# um982.net
KiCad netlist of a schematic drawn in Altium Designer
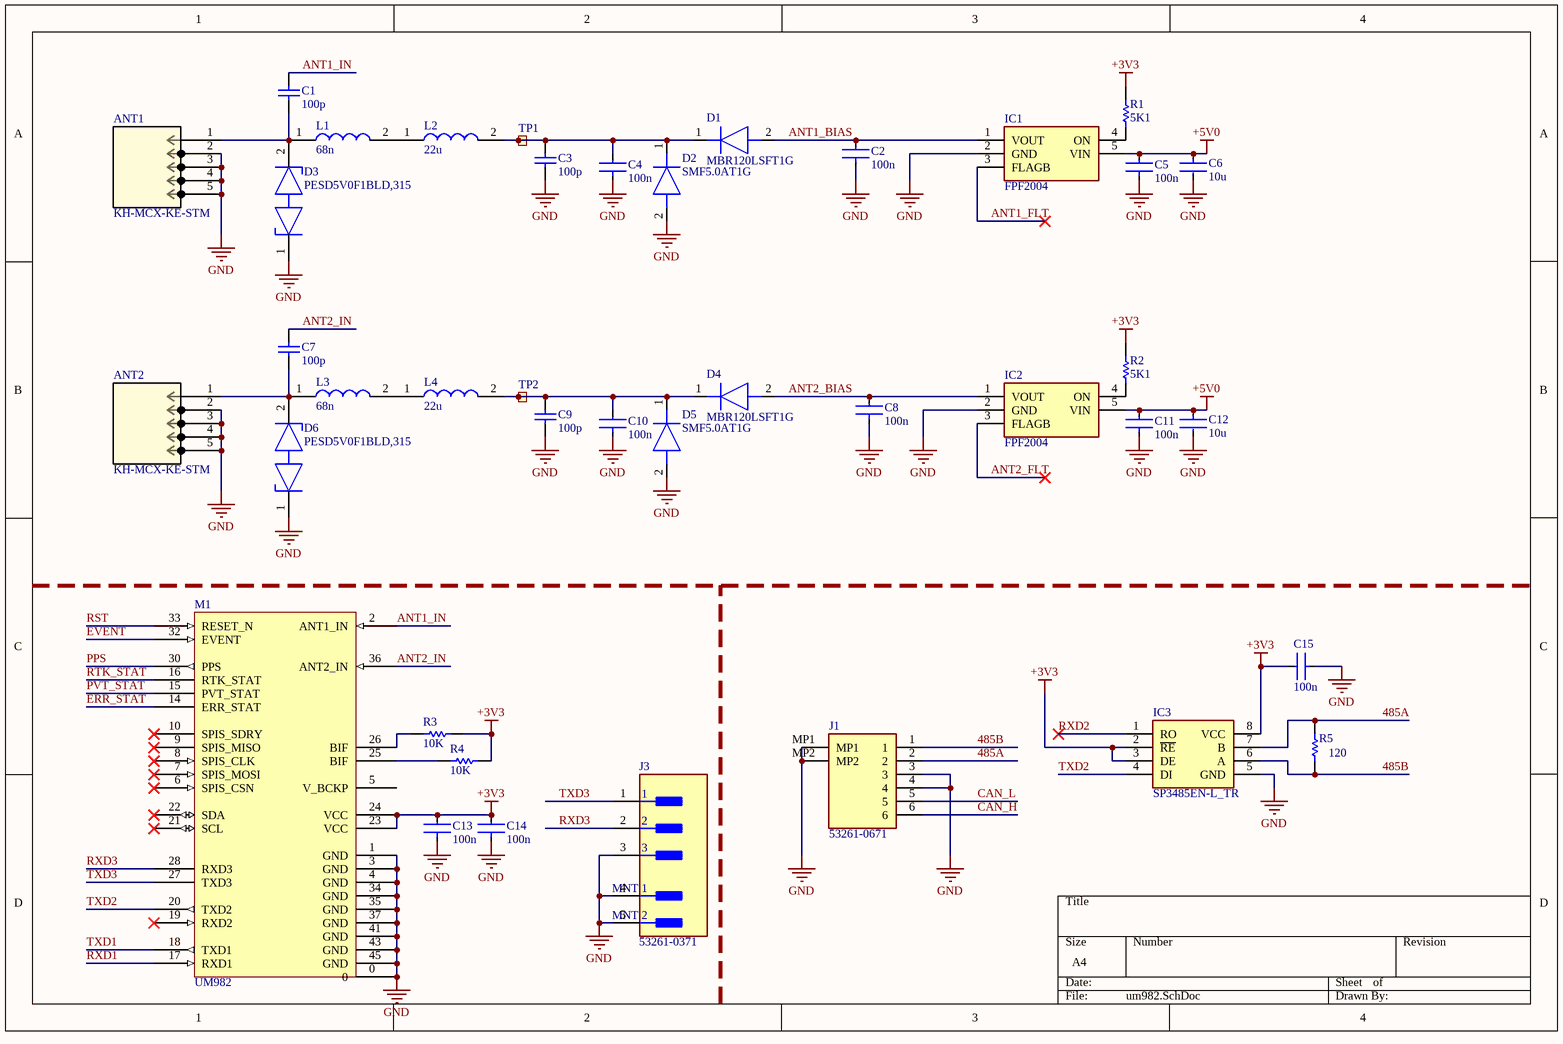
[diagram p0: um982.SchDoc]

(export (version "E")
  (design (tool "Eeschema 10.0.6"))
  (components
    (comp (ref "ANT1")
      (value "KH-MCX-KE-STM")
      (footprint "MCX-SMD_KH-MCX-KE-STM")
      (description "No Description Available")
      (fields
        (field (name "MANUFACTURER_PART_NUMBER") "919-415J-71P12G")
        (field (name "COPYRIGHT") "Copyright (C) 2025 Ultra Librarian. All rights reserved.")
      )
      (libsource (lib "UM982") (part "919-415J-71P12G"))
    )
    (comp (ref "ANT2")
      (value "KH-MCX-KE-STM")
      (footprint "MCX-SMD_KH-MCX-KE-STM")
      (description "No Description Available")
      (fields
        (field (name "MANUFACTURER_PART_NUMBER") "919-415J-71P12G")
        (field (name "COPYRIGHT") "Copyright (C) 2025 Ultra Librarian. All rights reserved.")
      )
      (libsource (lib "UM982") (part "919-415J-71P12G"))
    )
    (comp (ref "C1")
      (value "100p")
      (footprint "CAPC1005X55X25ML05T10")
      (fields (field (name "MANUFACTURER") "Murata") (field (name "PART NUMBER") "GRM1555C1H101JA01D"))
      (libsource (lib "Altium Content Vault") (part "CAP"))
    )
    (comp (ref "C2")
      (value "100n")
      (footprint "FP-C1005-050-0_05-IPC_C")
      (description "Multilayer Ceramic Capacitors 100nF ±10% 50V X7R SMD 0402")
      (fields (field (name "VOLTAGE") "50V") (field (name "TOLERANCE") "10%"))
      (libsource (lib "Altium Content Vault") (part "b4654b650e69147ec39a6b967a45e02"))
    )
    (comp (ref "C3")
      (value "100p")
      (footprint "CAPC1005X55X25ML05T10")
      (fields (field (name "MANUFACTURER") "Murata") (field (name "PART NUMBER") "GRM1555C1H101JA01D"))
      (libsource (lib "Altium Content Vault") (part "CAP"))
    )
    (comp (ref "C4")
      (value "100n")
      (footprint "FP-C1005-050-0_05-IPC_A")
      (description "Multilayer Ceramic Capacitors 100nF ±10% 50V X7R SMD 0402")
      (fields (field (name "VOLTAGE") "50V") (field (name "TOLERANCE") "10%"))
      (libsource (lib "Altium Content Vault") (part "b4654b650e69147ec39a6b967a45e02"))
    )
    (comp (ref "C5")
      (value "100n")
      (footprint "FP-C1005-050-0_05-IPC_C")
      (description "Multilayer Ceramic Capacitors 100nF ±10% 50V X7R SMD 0402")
      (fields (field (name "VOLTAGE") "50V") (field (name "TOLERANCE") "10%"))
      (libsource (lib "Altium Content Vault") (part "b4654b650e69147ec39a6b967a45e02"))
    )
    (comp (ref "C6")
      (value "10u")
      (footprint "FP-C1608-080-IPC_A")
      (description "CAP CER 10UF 25V X5R 0603")
      (fields (field (name "TOLERANCE") "20%") (field (name "Comment") "C1608X5R1E106M080AC"))
      (libsource (lib "Altium Content Vault") (part "11868f565c42a9108669ba33697ecf6"))
    )
    (comp (ref "C7")
      (value "100p")
      (footprint "CAPC1005X55X25ML05T10")
      (fields (field (name "MANUFACTURER") "Murata") (field (name "PART NUMBER") "GRM1555C1H101JA01D"))
      (libsource (lib "Altium Content Vault") (part "CAP"))
    )
    (comp (ref "C8")
      (value "100n")
      (footprint "FP-C1005-050-0_05-IPC_C")
      (description "Multilayer Ceramic Capacitors 100nF ±10% 50V X7R SMD 0402")
      (fields (field (name "VOLTAGE") "50V") (field (name "TOLERANCE") "10%"))
      (libsource (lib "Altium Content Vault") (part "b4654b650e69147ec39a6b967a45e02"))
    )
    (comp (ref "C9")
      (value "100p")
      (footprint "CAPC1005X55X25ML05T10")
      (fields (field (name "MANUFACTURER") "Murata") (field (name "PART NUMBER") "GRM1555C1H101JA01D"))
      (libsource (lib "Altium Content Vault") (part "CAP"))
    )
    (comp (ref "C10")
      (value "100n")
      (footprint "FP-C1005-050-0_05-IPC_A")
      (description "Multilayer Ceramic Capacitors 100nF ±10% 50V X7R SMD 0402")
      (fields (field (name "VOLTAGE") "50V") (field (name "TOLERANCE") "10%"))
      (libsource (lib "Altium Content Vault") (part "b4654b650e69147ec39a6b967a45e02"))
    )
    (comp (ref "C11")
      (value "100n")
      (footprint "FP-C1005-050-0_05-IPC_C")
      (description "Multilayer Ceramic Capacitors 100nF ±10% 50V X7R SMD 0402")
      (fields (field (name "VOLTAGE") "50V") (field (name "TOLERANCE") "10%"))
      (libsource (lib "Altium Content Vault") (part "b4654b650e69147ec39a6b967a45e02"))
    )
    (comp (ref "C12")
      (value "10u")
      (footprint "FP-C1608-080-IPC_A")
      (description "CAP CER 10UF 25V X5R 0603")
      (fields (field (name "TOLERANCE") "20%") (field (name "Comment") "C1608X5R1E106M080AC"))
      (libsource (lib "Altium Content Vault") (part "11868f565c42a9108669ba33697ecf6"))
    )
    (comp (ref "C13")
      (value "100n")
      (footprint "FP-C1005-050-0_05-IPC_A")
      (description "Multilayer Ceramic Capacitors 100nF ±10% 50V X7R SMD 0402")
      (fields (field (name "VOLTAGE") "50V") (field (name "TOLERANCE") "10%"))
      (libsource (lib "Altium Content Vault") (part "b4654b650e69147ec39a6b967a45e02"))
    )
    (comp (ref "C14")
      (value "100n")
      (footprint "FP-C1005-050-0_05-IPC_A")
      (description "Multilayer Ceramic Capacitors 100nF ±10% 50V X7R SMD 0402")
      (fields (field (name "VOLTAGE") "50V") (field (name "TOLERANCE") "10%"))
      (libsource (lib "Altium Content Vault") (part "b4654b650e69147ec39a6b967a45e02"))
    )
    (comp (ref "C15")
      (value "100n")
      (footprint "FP-C1005-050-0_05-IPC_C")
      (description "Multilayer Ceramic Capacitors 100nF ±10% 50V X7R SMD 0402")
      (fields (field (name "VOLTAGE") "50V") (field (name "TOLERANCE") "10%"))
      (libsource (lib "Altium Content Vault") (part "b4654b650e69147ec39a6b967a45e02"))
    )
    (comp (ref "D1")
      (value "MBR120LSFT1G")
      (footprint "SamacSys:SODFL3616X98N")
      (description "Diode")
      (fields (field (name "MOUSER PART NUMBER") "863-MBR120LSFT1G"))
      (libsource (lib "*") (part "MBR120LSFT1G"))
    )
    (comp (ref "D2")
      (value "SMF5.0AT1G")
      (footprint "SamacSys:SODFL3616X98N")
      (description "Diode")
      (fields (field (name "MOUSER PART NUMBER") "863-SMF5.0AT1G"))
      (libsource (lib "*") (part "SMF5.0AT1G"))
    )
    (comp (ref "D3")
      (value "PESD5V0F1BLD,315")
      (footprint "FP-SOD882D-MFG")
      (description "TVS DIODE 5.5V 15V 2DFN1006D")
      (libsource (lib "Altium Content Vault") (part "76a895bf0735dc68486ae99620ec8f1"))
    )
    (comp (ref "D4")
      (value "MBR120LSFT1G")
      (footprint "SamacSys:SODFL3616X98N")
      (description "Diode")
      (fields (field (name "MOUSER PART NUMBER") "863-MBR120LSFT1G"))
      (libsource (lib "*") (part "MBR120LSFT1G"))
    )
    (comp (ref "D5")
      (value "SMF5.0AT1G")
      (footprint "SamacSys:SODFL3616X98N")
      (description "Diode")
      (fields (field (name "MOUSER PART NUMBER") "863-SMF5.0AT1G"))
      (libsource (lib "*") (part "SMF5.0AT1G"))
    )
    (comp (ref "D6")
      (value "PESD5V0F1BLD,315")
      (footprint "FP-SOD882D-MFG")
      (description "TVS DIODE 5.5V 15V 2DFN1006D")
      (libsource (lib "Altium Content Vault") (part "76a895bf0735dc68486ae99620ec8f1"))
    )
    (comp (ref "IC1")
      (value "FPF2004")
      (footprint "SamacSys:SOT65P210X110-5N")
      (description "Integrated Circuit")
      (fields (field (name "MOUSER PART NUMBER") "512-FPF2004"))
      (libsource (lib "*") (part "FPF2004"))
    )
    (comp (ref "IC2")
      (value "FPF2004")
      (footprint "SamacSys:SOT65P210X110-5N")
      (description "Integrated Circuit")
      (fields (field (name "MOUSER PART NUMBER") "512-FPF2004"))
      (libsource (lib "*") (part "FPF2004"))
    )
    (comp (ref "IC3")
      (value "SP3485EN-L_TR")
      (footprint "SamacSys:SOIC127P600X175-8N")
      (description "Integrated Circuit")
      (fields
        (field (name "MANUFACTURER_PART_NUMBER") "SP3485EN-L/TR")
        (field (name "MOUSER PART NUMBER") "701-SP3485EN-L/TR")
      )
      (libsource (lib "*") (part "SP3485EN-L_TR"))
    )
    (comp (ref "J1")
      (value "53261-0671")
      (footprint "SamacSys:532610671")
      (description "Connector")
      (fields (field (name "MOUSER PART NUMBER") "538-53261-0671"))
      (libsource (lib "*") (part "53261-0671"))
    )
    (comp (ref "J3")
      (value "53261-0371")
      (footprint "FP-53261-0371-MFG")
      (description "CONN HEADER SMD R/A 3POS 1.25MM")
      (fields
        (field (name "MANUFACTURER") "Molex")
        (field (name "OCTOPART") "https://octopart.com/53261-0371-molex-655314")
      )
      (libsource (lib "Altium Content Vault") (part "13850a6865a90496d8e6d51657cef87"))
    )
    (comp (ref "L1")
      (value "68n")
      (footprint "SamacSys:LQG15WH0N7B02D")
      (description "Inductor")
      (fields
        (field (name "MANUFACTURER_PART_NUMBER") "LQG15HS68NJ02D")
        (field (name "MOUSER PART NUMBER") "81-LQG15HS68NJ02D")
      )
      (libsource (lib "*") (part "LQG15HS68NJ02D"))
    )
    (comp (ref "L2")
      (value "22u")
      (footprint "SamacSys:INDM4532X340N")
      (description "Inductor")
      (fields
        (field (name "MANUFACTURER_PART_NUMBER") "NL453232T-220J-PF")
        (field (name "MOUSER PART NUMBER") "810-NL453232T-220JPF")
      )
      (libsource (lib "*") (part "NL453232T-220J-PF"))
    )
    (comp (ref "L3")
      (value "68n")
      (footprint "SamacSys:LQG15WH0N7B02D")
      (description "Inductor")
      (fields
        (field (name "MANUFACTURER_PART_NUMBER") "LQG15HS68NJ02D")
        (field (name "MOUSER PART NUMBER") "81-LQG15HS68NJ02D")
      )
      (libsource (lib "*") (part "LQG15HS68NJ02D"))
    )
    (comp (ref "L4")
      (value "22u")
      (footprint "SamacSys:INDM4532X340N")
      (description "Inductor")
      (fields
        (field (name "MANUFACTURER_PART_NUMBER") "NL453232T-220J-PF")
        (field (name "MOUSER PART NUMBER") "810-NL453232T-220JPF")
      )
      (libsource (lib "*") (part "NL453232T-220J-PF"))
    )
    (comp (ref "M1")
      (value "UM982")
      (footprint "UM982")
      (description "All-constellation Multi-frequencyHigh Precision Positioning & Heading Module")
      (libsource (lib "UM982") (part "UM982"))
    )
    (comp (ref "R1")
      (value "5K1")
      (footprint "RESC1005X40X25NL05T10")
      (fields (field (name "PART NUMBER") "RC0402FR-075K1L") (field (name "MANUFACTURER") "Yageo / Phycomp"))
      (libsource (lib "Altium Content Vault") (part "RES"))
    )
    (comp (ref "R2")
      (value "5K1")
      (footprint "RESC1005X40X25NL05T10")
      (fields (field (name "PART NUMBER") "RC0402FR-075K1L") (field (name "MANUFACTURER") "Yageo / Phycomp"))
      (libsource (lib "Altium Content Vault") (part "RES"))
    )
    (comp (ref "R3")
      (value "10K")
      (footprint "RESC1005X40X25LL05T10")
      (fields (field (name "PART NUMBER") "RC0402FR-0710KL") (field (name "MANUFACTURER") "Yageo / Phycomp"))
      (libsource (lib "Altium Content Vault") (part "RES"))
    )
    (comp (ref "R4")
      (value "10K")
      (footprint "RESC1005X40X25LL05T10")
      (fields (field (name "PART NUMBER") "RC0402FR-0710KL") (field (name "MANUFACTURER") "Yageo / Phycomp"))
      (libsource (lib "Altium Content Vault") (part "RES"))
    )
    (comp (ref "R5")
      (value "120")
      (footprint "RESC1005X40X25NL05T10")
      (fields (field (name "MANUFACTURER") "Yageo / Phycomp") (field (name "PART NUMBER") "RC0402FR-07120RL"))
      (libsource (lib "Altium Content Vault") (part "RES"))
    )
    (comp (ref "TP1")
      (value "Ø1.0mm,SMD")
      (footprint "TP_SMD_Ø1.0mm")
      (description "1.0mm circular SMD testpad")
      (fields
        (field (name "PART NUMBER") "TP_SMD_Ø1.0MM")
        (field (name "MANUFACTURER") "Nordic Semiconductor")
      )
      (libsource (lib "ParsaLibrary") (part "TP_SMD_Ø1.0MM"))
    )
    (comp (ref "TP2")
      (value "Ø1.0mm,SMD")
      (footprint "TP_SMD_Ø1.0mm")
      (description "1.0mm circular SMD testpad")
      (fields
        (field (name "PART NUMBER") "TP_SMD_Ø1.0MM")
        (field (name "MANUFACTURER") "Nordic Semiconductor")
      )
      (libsource (lib "ParsaLibrary") (part "TP_SMD_Ø1.0MM"))
    )
  )
  (nets
    (net (code "1") (name "+3V3") (class "Default")
      (node (ref "C13") (pin "2") (pinfunction "2_2") (pintype "passive"))
      (node (ref "C14") (pin "2") (pinfunction "2_2") (pintype "passive"))
      (node (ref "C15") (pin "2") (pinfunction "2_2") (pintype "passive"))
      (node (ref "IC3") (pin "2") (pinfunction "~{RE}_2") (pintype "passive"))
      (node (ref "IC3") (pin "3") (pinfunction "DE_3") (pintype "passive"))
      (node (ref "IC3") (pin "8") (pinfunction "VCC_8") (pintype "passive"))
      (node (ref "M1") (pin "23") (pinfunction "VCC_23") (pintype "power_in"))
      (node (ref "M1") (pin "24") (pinfunction "VCC_24") (pintype "power_in"))
      (node (ref "R1") (pin "1") (pinfunction "1_1") (pintype "passive"))
      (node (ref "R2") (pin "1") (pinfunction "1_1") (pintype "passive"))
      (node (ref "R3") (pin "1") (pinfunction "1_1") (pintype "passive"))
      (node (ref "R4") (pin "1") (pinfunction "1_1") (pintype "passive"))
    )
    (net (code "2") (name "+5V0") (class "Default")
      (node (ref "C11") (pin "2") (pinfunction "2_2") (pintype "passive"))
      (node (ref "C12") (pin "1") (pinfunction "1_1") (pintype "passive"))
      (node (ref "C5") (pin "2") (pinfunction "2_2") (pintype "passive"))
      (node (ref "C6") (pin "1") (pinfunction "1_1") (pintype "passive"))
      (node (ref "IC1") (pin "5") (pinfunction "VIN_5") (pintype "passive"))
      (node (ref "IC2") (pin "5") (pinfunction "VIN_5") (pintype "passive"))
    )
    (net (code "3") (name "/485A") (class "Default")
      (node (ref "IC3") (pin "7") (pinfunction "B_7") (pintype "passive"))
      (node (ref "J1") (pin "2") (pinfunction "2_2") (pintype "passive"))
      (node (ref "R5") (pin "2") (pinfunction "2_2") (pintype "passive"))
    )
    (net (code "4") (name "/485B") (class "Default")
      (node (ref "IC3") (pin "6") (pinfunction "A_6") (pintype "passive"))
      (node (ref "J1") (pin "1") (pinfunction "1_1") (pintype "passive"))
      (node (ref "R5") (pin "1") (pinfunction "1_1") (pintype "passive"))
    )
    (net (code "5") (name "/ANT1_BIAS") (class "Default")
      (node (ref "C2") (pin "2") (pinfunction "2_2") (pintype "passive"))
      (node (ref "D1") (pin "2") (pinfunction "A_2") (pintype "passive"))
      (node (ref "IC1") (pin "1") (pinfunction "VOUT_1") (pintype "passive"))
    )
    (net (code "6") (name "/ANT1_FLT") (class "Default")
      (node (ref "IC1") (pin "3") (pinfunction "FLAGB_3") (pintype "passive+no_connect"))
    )
    (net (code "7") (name "/ANT1_IN") (class "Default")
      (node (ref "C1") (pin "2") (pinfunction "2_2") (pintype "passive"))
      (node (ref "M1") (pin "2") (pinfunction "ANT1_IN_2") (pintype "input"))
    )
    (net (code "8") (name "/ANT2_BIAS") (class "Default")
      (node (ref "C8") (pin "2") (pinfunction "2_2") (pintype "passive"))
      (node (ref "D4") (pin "2") (pinfunction "A_2") (pintype "passive"))
      (node (ref "IC2") (pin "1") (pinfunction "VOUT_1") (pintype "passive"))
    )
    (net (code "9") (name "/ANT2_FLT") (class "Default")
      (node (ref "IC2") (pin "3") (pinfunction "FLAGB_3") (pintype "passive+no_connect"))
    )
    (net (code "10") (name "/ANT2_IN") (class "Default")
      (node (ref "C7") (pin "2") (pinfunction "2_2") (pintype "passive"))
      (node (ref "M1") (pin "36") (pinfunction "ANT2_IN_36") (pintype "input"))
    )
    (net (code "11") (name "/CAN_H") (class "Default")
      (node (ref "J1") (pin "6") (pinfunction "6_6") (pintype "passive"))
    )
    (net (code "12") (name "/CAN_L") (class "Default")
      (node (ref "J1") (pin "5") (pinfunction "5_5") (pintype "passive"))
    )
    (net (code "13") (name "/ERR_STAT") (class "Default")
      (node (ref "M1") (pin "14") (pinfunction "ERR_STAT_14") (pintype "passive"))
    )
    (net (code "14") (name "/EVENT") (class "Default")
      (node (ref "M1") (pin "32") (pinfunction "EVENT_32") (pintype "input"))
    )
    (net (code "15") (name "/PPS") (class "Default")
      (node (ref "M1") (pin "30") (pinfunction "PPS_30") (pintype "output"))
    )
    (net (code "16") (name "/PVT_STAT") (class "Default")
      (node (ref "M1") (pin "15") (pinfunction "PVT_STAT_15") (pintype "passive"))
    )
    (net (code "17") (name "/RST") (class "Default")
      (node (ref "M1") (pin "33") (pinfunction "RESET_N_33") (pintype "input"))
    )
    (net (code "18") (name "/RTK_STAT") (class "Default")
      (node (ref "M1") (pin "16") (pinfunction "RTK_STAT_16") (pintype "passive"))
    )
    (net (code "19") (name "/RXD1") (class "Default")
      (node (ref "M1") (pin "17") (pinfunction "RXD1_17") (pintype "input"))
    )
    (net (code "20") (name "/RXD2") (class "Default")
      (node (ref "IC3") (pin "1") (pinfunction "RO_1") (pintype "passive+no_connect"))
    )
    (net (code "21") (name "/RXD3") (class "Default")
      (node (ref "J3") (pin "2") (pinfunction "2_2") (pintype "passive"))
      (node (ref "M1") (pin "28") (pinfunction "RXD3_28") (pintype "passive"))
    )
    (net (code "22") (name "/TXD1") (class "Default")
      (node (ref "M1") (pin "18") (pinfunction "TXD1_18") (pintype "output"))
    )
    (net (code "23") (name "/TXD2") (class "Default")
      (node (ref "IC3") (pin "4") (pinfunction "DI_4") (pintype "passive"))
      (node (ref "M1") (pin "20") (pinfunction "TXD2_20") (pintype "output"))
    )
    (net (code "24") (name "/TXD3") (class "Default")
      (node (ref "J3") (pin "1") (pinfunction "1_1") (pintype "passive"))
      (node (ref "M1") (pin "27") (pinfunction "TXD3_27") (pintype "passive"))
    )
    (net (code "25") (name "GND") (class "Default")
      (node (ref "ANT1") (pin "2") (pinfunction "______GND_2") (pintype "passive"))
      (node (ref "ANT1") (pin "3") (pinfunction "______GND_3") (pintype "passive"))
      (node (ref "ANT1") (pin "4") (pinfunction "______GND_4") (pintype "passive"))
      (node (ref "ANT1") (pin "5") (pinfunction "______GND_5") (pintype "passive"))
      (node (ref "ANT2") (pin "2") (pinfunction "______GND_2") (pintype "passive"))
      (node (ref "ANT2") (pin "3") (pinfunction "______GND_3") (pintype "passive"))
      (node (ref "ANT2") (pin "4") (pinfunction "______GND_4") (pintype "passive"))
      (node (ref "ANT2") (pin "5") (pinfunction "______GND_5") (pintype "passive"))
      (node (ref "C10") (pin "1") (pinfunction "1_1") (pintype "passive"))
      (node (ref "C11") (pin "1") (pinfunction "1_1") (pintype "passive"))
      (node (ref "C12") (pin "2") (pinfunction "2_2") (pintype "passive"))
      (node (ref "C13") (pin "1") (pinfunction "1_1") (pintype "passive"))
      (node (ref "C14") (pin "1") (pinfunction "1_1") (pintype "passive"))
      (node (ref "C15") (pin "1") (pinfunction "1_1") (pintype "passive"))
      (node (ref "C2") (pin "1") (pinfunction "1_1") (pintype "passive"))
      (node (ref "C3") (pin "2") (pinfunction "2_2") (pintype "passive"))
      (node (ref "C4") (pin "1") (pinfunction "1_1") (pintype "passive"))
      (node (ref "C5") (pin "1") (pinfunction "1_1") (pintype "passive"))
      (node (ref "C6") (pin "2") (pinfunction "2_2") (pintype "passive"))
      (node (ref "C8") (pin "1") (pinfunction "1_1") (pintype "passive"))
      (node (ref "C9") (pin "2") (pinfunction "2_2") (pintype "passive"))
      (node (ref "D2") (pin "2") (pinfunction "A_2") (pintype "passive"))
      (node (ref "D3") (pin "1") (pinfunction "cathode(diode_1)_1") (pintype "passive"))
      (node (ref "D5") (pin "2") (pinfunction "A_2") (pintype "passive"))
      (node (ref "D6") (pin "1") (pinfunction "cathode(diode_1)_1") (pintype "passive"))
      (node (ref "IC1") (pin "2") (pinfunction "GND_2") (pintype "passive"))
      (node (ref "IC2") (pin "2") (pinfunction "GND_2") (pintype "passive"))
      (node (ref "IC3") (pin "5") (pinfunction "GND_5") (pintype "passive"))
      (node (ref "J1") (pin "3") (pinfunction "3_3") (pintype "passive"))
      (node (ref "J1") (pin "4") (pinfunction "4_4") (pintype "passive"))
      (node (ref "J1") (pin "MP1") (pinfunction "MP1_MP1") (pintype "passive"))
      (node (ref "J1") (pin "MP2") (pinfunction "MP2_MP2") (pintype "passive"))
      (node (ref "J3") (pin "3") (pinfunction "3_3") (pintype "passive"))
      (node (ref "J3") (pin "4") (pinfunction "MNT_1_4") (pintype "passive"))
      (node (ref "J3") (pin "5") (pinfunction "MNT_2_5") (pintype "passive"))
      (node (ref "M1") (pin "0") (pinfunction "0_0") (pintype "passive"))
      (node (ref "M1") (pin "1") (pinfunction "GND_1") (pintype "passive"))
      (node (ref "M1") (pin "3") (pinfunction "GND_3") (pintype "passive"))
      (node (ref "M1") (pin "34") (pinfunction "GND_34") (pintype "passive"))
      (node (ref "M1") (pin "35") (pinfunction "GND_35") (pintype "passive"))
      (node (ref "M1") (pin "37") (pinfunction "GND_37") (pintype "passive"))
      (node (ref "M1") (pin "4") (pinfunction "GND_4") (pintype "passive"))
      (node (ref "M1") (pin "41") (pinfunction "GND_41") (pintype "passive"))
      (node (ref "M1") (pin "43") (pinfunction "GND_43") (pintype "passive"))
      (node (ref "M1") (pin "45") (pinfunction "GND_45") (pintype "passive"))
    )
    (net (code "26") (name "Net-(ANT1-______SIGNAL)") (class "Default")
      (node (ref "ANT1") (pin "1") (pinfunction "______SIGNAL_1") (pintype "passive"))
      (node (ref "C1") (pin "1") (pinfunction "1_1") (pintype "passive"))
      (node (ref "D3") (pin "2") (pinfunction "cathode(diode_2)_2") (pintype "passive"))
      (node (ref "L1") (pin "1") (pinfunction "1_1") (pintype "passive"))
    )
    (net (code "27") (name "Net-(ANT2-______SIGNAL)") (class "Default")
      (node (ref "ANT2") (pin "1") (pinfunction "______SIGNAL_1") (pintype "passive"))
      (node (ref "C7") (pin "1") (pinfunction "1_1") (pintype "passive"))
      (node (ref "D6") (pin "2") (pinfunction "cathode(diode_2)_2") (pintype "passive"))
      (node (ref "L3") (pin "1") (pinfunction "1_1") (pintype "passive"))
    )
    (net (code "28") (name "Net-(D1-K)") (class "Default")
      (node (ref "C3") (pin "1") (pinfunction "1_1") (pintype "passive"))
      (node (ref "C4") (pin "2") (pinfunction "2_2") (pintype "passive"))
      (node (ref "D1") (pin "1") (pinfunction "K_1") (pintype "passive"))
      (node (ref "D2") (pin "1") (pinfunction "K_1") (pintype "passive"))
      (node (ref "L2") (pin "2") (pinfunction "2_2") (pintype "passive"))
      (node (ref "TP1") (pin "1") (pinfunction "1_1") (pintype "passive"))
    )
    (net (code "29") (name "Net-(D4-K)") (class "Default")
      (node (ref "C10") (pin "2") (pinfunction "2_2") (pintype "passive"))
      (node (ref "C9") (pin "1") (pinfunction "1_1") (pintype "passive"))
      (node (ref "D4") (pin "1") (pinfunction "K_1") (pintype "passive"))
      (node (ref "D5") (pin "1") (pinfunction "K_1") (pintype "passive"))
      (node (ref "L4") (pin "2") (pinfunction "2_2") (pintype "passive"))
      (node (ref "TP2") (pin "1") (pinfunction "1_1") (pintype "passive"))
    )
    (net (code "30") (name "Net-(IC1-ON)") (class "Default")
      (node (ref "IC1") (pin "4") (pinfunction "ON_4") (pintype "passive"))
      (node (ref "R1") (pin "2") (pinfunction "2_2") (pintype "passive"))
    )
    (net (code "31") (name "Net-(IC2-ON)") (class "Default")
      (node (ref "IC2") (pin "4") (pinfunction "ON_4") (pintype "passive"))
      (node (ref "R2") (pin "2") (pinfunction "2_2") (pintype "passive"))
    )
    (net (code "32") (name "Net-(L1-Pad2)") (class "Default")
      (node (ref "L1") (pin "2") (pinfunction "2_2") (pintype "passive"))
      (node (ref "L2") (pin "1") (pinfunction "1_1") (pintype "passive"))
    )
    (net (code "33") (name "Net-(L3-Pad2)") (class "Default")
      (node (ref "L3") (pin "2") (pinfunction "2_2") (pintype "passive"))
      (node (ref "L4") (pin "1") (pinfunction "1_1") (pintype "passive"))
    )
    (net (code "34") (name "Net-(M1-BIF-Pad25)") (class "Default")
      (node (ref "M1") (pin "25") (pinfunction "BIF_25") (pintype "passive"))
      (node (ref "R4") (pin "2") (pinfunction "2_2") (pintype "passive"))
    )
    (net (code "35") (name "Net-(M1-BIF-Pad26)") (class "Default")
      (node (ref "M1") (pin "26") (pinfunction "BIF_26") (pintype "passive"))
      (node (ref "R3") (pin "2") (pinfunction "2_2") (pintype "passive"))
    )
    (net (code "36") (name "unconnected-(M1-RXD2-Pad19)") (class "Default")
      (node (ref "M1") (pin "19") (pinfunction "RXD2_19") (pintype "input+no_connect"))
    )
    (net (code "37") (name "unconnected-(M1-SCL-Pad21)") (class "Default")
      (node (ref "M1") (pin "21") (pinfunction "SCL_21") (pintype "bidirectional+no_connect"))
    )
    (net (code "38") (name "unconnected-(M1-SDA-Pad22)") (class "Default")
      (node (ref "M1") (pin "22") (pinfunction "SDA_22") (pintype "bidirectional+no_connect"))
    )
    (net (code "39") (name "unconnected-(M1-SPIS_CLK-Pad8)") (class "Default")
      (node (ref "M1") (pin "8") (pinfunction "SPIS_CLK_8") (pintype "input+no_connect"))
    )
    (net (code "40") (name "unconnected-(M1-SPIS_CSN-Pad6)") (class "Default")
      (node (ref "M1") (pin "6") (pinfunction "SPIS_CSN_6") (pintype "input+no_connect"))
    )
    (net (code "41") (name "unconnected-(M1-SPIS_MISO-Pad9)") (class "Default")
      (node (ref "M1") (pin "9") (pinfunction "SPIS_MISO_9") (pintype "passive+no_connect"))
    )
    (net (code "42") (name "unconnected-(M1-SPIS_MOSI-Pad7)") (class "Default")
      (node (ref "M1") (pin "7") (pinfunction "SPIS_MOSI_7") (pintype "input+no_connect"))
    )
    (net (code "43") (name "unconnected-(M1-SPIS_SDRY-Pad10)") (class "Default")
      (node (ref "M1") (pin "10") (pinfunction "SPIS_SDRY_10") (pintype "passive+no_connect"))
    )
    (net (code "44") (name "unconnected-(M1-V_BCKP-Pad5)") (class "Default")
      (node (ref "M1") (pin "5") (pinfunction "V_BCKP_5") (pintype "passive"))
    )
  )
)
